# FiltrosGyrator_SCH.net
KiCad netlist of a schematic drawn in Altium Designer
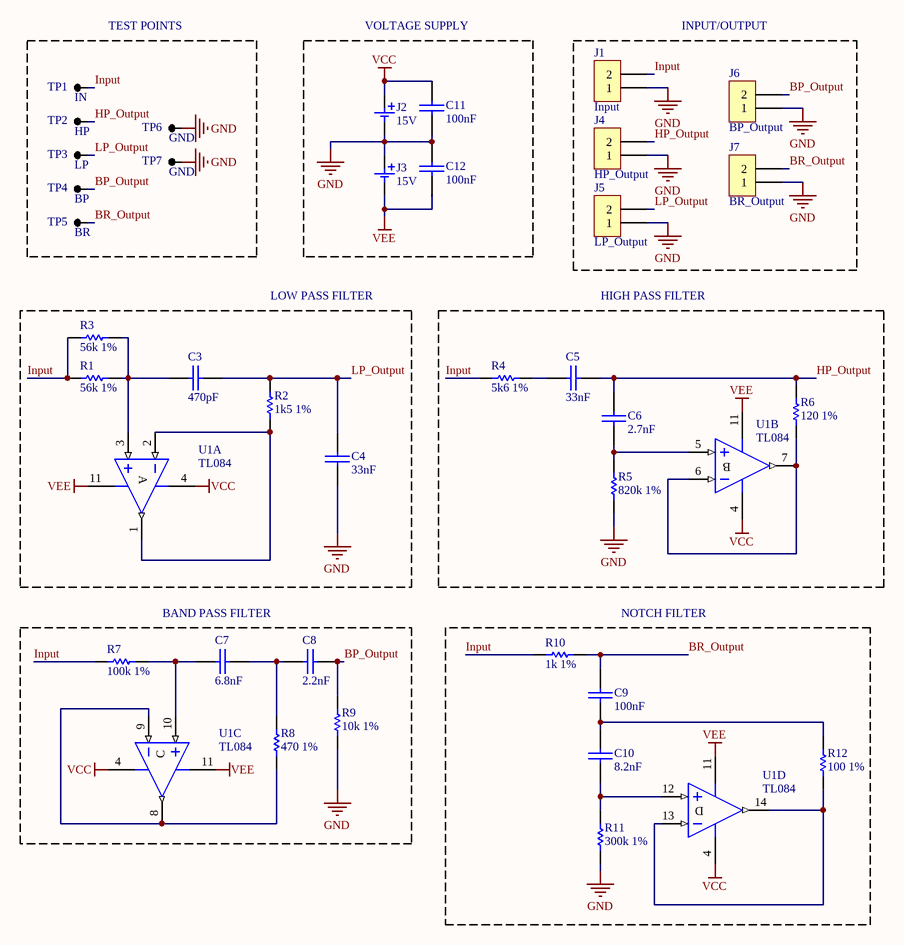
[diagram p0: FiltrosGyrator_SCH.SchDoc]

(export (version "E")
  (design (tool "Eeschema 10.0.6"))
  (components
    (comp (ref "C3")
      (value "470pF")
      (footprint "CAP_470p_CERAMIC_THT")
      (libsource (lib "LIBEBAL") (part "CAP"))
    )
    (comp (ref "C4") (value "33nF") (footprint "CAP_33N_FILM_THT") (libsource (lib "LIBEBAL") (part "CAP")))
    (comp (ref "C5") (value "33nF") (footprint "CAP_33N_FILM_THT") (libsource (lib "LIBEBAL") (part "CAP")))
    (comp (ref "C6") (value "2.7nF") (footprint "CAP_2.7n_FILM_THT") (libsource (lib "LIBEBAL") (part "CAP")))
    (comp (ref "C7") (value "6.8nF") (footprint "CAP_6.8n_FILM_THT") (libsource (lib "LIBEBAL") (part "CAP")))
    (comp (ref "C8") (value "2.2nF") (footprint "CAP_8.2n_FILM_THT") (libsource (lib "LIBEBAL") (part "CAP")))
    (comp (ref "C9") (value "100nF") (footprint "CAP_10N_FILM_THT") (libsource (lib "LIBEBAL") (part "CAP")))
    (comp (ref "C10")
      (value "8.2nF")
      (footprint "CAP_8.2n_FILM_THT")
      (libsource (lib "LIBEBAL") (part "CAP"))
    )
    (comp (ref "C11") (value "100nF") (footprint "0805") (libsource (lib "LIBEBAL") (part "CAP")))
    (comp (ref "C12") (value "100nF") (footprint "0805") (libsource (lib "LIBEBAL") (part "CAP")))
    (comp (ref "J1") (value "Input") (footprint "BORNERA2") (libsource (lib "LIB PIO IX") (part "BORNERA 2")))
    (comp (ref "J2")
      (value "15V")
      (footprint "BORNERA2")
      (description "BATERIA")
      (libsource (lib "LIBEBAL") (part "BATERIA"))
    )
    (comp (ref "J3")
      (value "15V")
      (footprint "BORNERA2")
      (description "BATERIA")
      (libsource (lib "LIBEBAL") (part "BATERIA"))
    )
    (comp (ref "J4")
      (value "HP_Output")
      (footprint "BORNERA2")
      (libsource (lib "LIB PIO IX") (part "BORNERA 2"))
    )
    (comp (ref "J5")
      (value "LP_Output")
      (footprint "BORNERA2")
      (libsource (lib "LIB PIO IX") (part "BORNERA 2"))
    )
    (comp (ref "J6")
      (value "BP_Output")
      (footprint "BORNERA2")
      (libsource (lib "LIB PIO IX") (part "BORNERA 2"))
    )
    (comp (ref "J7")
      (value "BR_Output")
      (footprint "BORNERA2")
      (libsource (lib "LIB PIO IX") (part "BORNERA 2"))
    )
    (comp (ref "R1") (value "56k 1%") (footprint "0805") (libsource (lib "LIBEBAL") (part "RES")))
    (comp (ref "R2") (value "1k5 1%") (footprint "0805") (libsource (lib "LIBEBAL") (part "RES")))
    (comp (ref "R3") (value "56k 1%") (footprint "0805") (libsource (lib "LIBEBAL") (part "RES")))
    (comp (ref "R4") (value "5k6 1%") (footprint "0805") (libsource (lib "LIBEBAL") (part "RES")))
    (comp (ref "R5") (value "820k 1%") (footprint "0805") (libsource (lib "LIBEBAL") (part "RES")))
    (comp (ref "R6") (value "120 1%") (footprint "0805") (libsource (lib "LIBEBAL") (part "RES")))
    (comp (ref "R7") (value "100k 1%") (footprint "0805") (libsource (lib "LIBEBAL") (part "RES")))
    (comp (ref "R8") (value "470 1%") (footprint "0805") (libsource (lib "LIBEBAL") (part "RES")))
    (comp (ref "R9") (value "10k 1%") (footprint "0805") (libsource (lib "LIBEBAL") (part "RES")))
    (comp (ref "R10") (value "1k 1%") (footprint "0805") (libsource (lib "LIBEBAL") (part "RES")))
    (comp (ref "R11") (value "300k 1%") (footprint "0805") (libsource (lib "LIBEBAL") (part "RES")))
    (comp (ref "R12") (value "100 1%") (footprint "0805") (libsource (lib "LIBEBAL") (part "RES")))
    (comp (ref "TP1") (value "IN") (footprint "TPTH") (libsource (lib "LIBEBAL") (part "TP")))
    (comp (ref "TP2") (value "HP") (footprint "TPTH") (libsource (lib "LIBEBAL") (part "TP")))
    (comp (ref "TP3") (value "LP") (footprint "TPTH") (libsource (lib "LIBEBAL") (part "TP")))
    (comp (ref "TP4") (value "BP") (footprint "TPTH") (libsource (lib "LIBEBAL") (part "TP")))
    (comp (ref "TP5") (value "BR") (footprint "TPTH") (libsource (lib "LIBEBAL") (part "TP")))
    (comp (ref "TP6") (value "GND") (footprint "TPTH") (libsource (lib "LIBEBAL") (part "TP")))
    (comp (ref "TP7") (value "GND") (footprint "TPTH") (libsource (lib "LIBEBAL") (part "TP")))
    (comp (ref "U1")
      (value "TL084")
      (footprint "J014")
      (description "JFET-Input Operational Amplifier")
      (fields (field (name "PUBLISHER") "Altium Limited"))
      (libsource (lib "FiltrosGyrator") (part "TL084J"))
    )
  )
  (nets
    (net (code "1") (name "/BP_Output") (class "Default")
      (node (ref "C8") (pin "2") (pinfunction "2_2") (pintype "passive"))
      (node (ref "J6") (pin "2") (pinfunction "2_2") (pintype "passive"))
      (node (ref "R9") (pin "2") (pinfunction "2_2") (pintype "passive"))
      (node (ref "TP4") (pin "1") (pinfunction "1_1") (pintype "passive"))
    )
    (net (code "2") (name "/BR_Output") (class "Default")
      (node (ref "C9") (pin "1") (pinfunction "1_1") (pintype "passive"))
      (node (ref "J7") (pin "2") (pinfunction "2_2") (pintype "passive"))
      (node (ref "R10") (pin "2") (pinfunction "2_2") (pintype "passive"))
      (node (ref "TP5") (pin "1") (pinfunction "1_1") (pintype "passive"))
    )
    (net (code "3") (name "/HP_Output") (class "Default")
      (node (ref "C5") (pin "2") (pinfunction "2_2") (pintype "passive"))
      (node (ref "C6") (pin "1") (pinfunction "1_1") (pintype "passive"))
      (node (ref "J4") (pin "2") (pinfunction "2_2") (pintype "passive"))
      (node (ref "R6") (pin "1") (pinfunction "1_1") (pintype "passive"))
      (node (ref "TP2") (pin "1") (pinfunction "1_1") (pintype "passive"))
    )
    (net (code "4") (name "/Input") (class "Default")
      (node (ref "J1") (pin "2") (pinfunction "2_2") (pintype "passive"))
      (node (ref "R1") (pin "1") (pinfunction "1_1") (pintype "passive"))
      (node (ref "R10") (pin "1") (pinfunction "1_1") (pintype "passive"))
      (node (ref "R3") (pin "1") (pinfunction "1_1") (pintype "passive"))
      (node (ref "R4") (pin "1") (pinfunction "1_1") (pintype "passive"))
      (node (ref "R7") (pin "1") (pinfunction "1_1") (pintype "passive"))
      (node (ref "TP1") (pin "1") (pinfunction "1_1") (pintype "passive"))
    )
    (net (code "5") (name "/LP_Output") (class "Default")
      (node (ref "C3") (pin "2") (pinfunction "2_2") (pintype "passive"))
      (node (ref "C4") (pin "2") (pinfunction "2_2") (pintype "passive"))
      (node (ref "J5") (pin "2") (pinfunction "2_2") (pintype "passive"))
      (node (ref "R2") (pin "2") (pinfunction "2_2") (pintype "passive"))
      (node (ref "TP3") (pin "1") (pinfunction "1_1") (pintype "passive"))
    )
    (net (code "6") (name "GND") (class "Default")
      (node (ref "C11") (pin "2") (pinfunction "2_2") (pintype "passive"))
      (node (ref "C12") (pin "1") (pinfunction "1_1") (pintype "passive"))
      (node (ref "C4") (pin "1") (pinfunction "1_1") (pintype "passive"))
      (node (ref "J1") (pin "1") (pinfunction "1_1") (pintype "passive"))
      (node (ref "J2") (pin "2") (pintype "passive"))
      (node (ref "J3") (pin "1") (pintype "passive"))
      (node (ref "J4") (pin "1") (pinfunction "1_1") (pintype "passive"))
      (node (ref "J5") (pin "1") (pinfunction "1_1") (pintype "passive"))
      (node (ref "J6") (pin "1") (pinfunction "1_1") (pintype "passive"))
      (node (ref "J7") (pin "1") (pinfunction "1_1") (pintype "passive"))
      (node (ref "R11") (pin "2") (pinfunction "2_2") (pintype "passive"))
      (node (ref "R5") (pin "1") (pinfunction "1_1") (pintype "passive"))
      (node (ref "R9") (pin "1") (pinfunction "1_1") (pintype "passive"))
      (node (ref "TP6") (pin "1") (pinfunction "1_1") (pintype "passive"))
      (node (ref "TP7") (pin "1") (pinfunction "1_1") (pintype "passive"))
    )
    (net (code "7") (name "Net-(C5-Pad1)") (class "Default")
      (node (ref "C5") (pin "1") (pinfunction "1_1") (pintype "passive"))
      (node (ref "R4") (pin "2") (pinfunction "2_2") (pintype "passive"))
    )
    (net (code "8") (name "Net-(C7-Pad2)") (class "Default")
      (node (ref "C7") (pin "2") (pinfunction "2_2") (pintype "passive"))
      (node (ref "C8") (pin "1") (pinfunction "1_1") (pintype "passive"))
      (node (ref "R8") (pin "2") (pinfunction "2_2") (pintype "passive"))
    )
    (net (code "9") (name "Net-(C10-Pad2)") (class "Default")
      (node (ref "C10") (pin "2") (pinfunction "2_2") (pintype "passive"))
      (node (ref "C9") (pin "2") (pinfunction "2_2") (pintype "passive"))
      (node (ref "R12") (pin "2") (pinfunction "2_2") (pintype "passive"))
    )
    (net (code "10") (name "Net-(U1A-IN+)") (class "Default")
      (node (ref "C3") (pin "1") (pinfunction "1_1") (pintype "passive"))
      (node (ref "R1") (pin "2") (pinfunction "2_2") (pintype "passive"))
      (node (ref "R3") (pin "2") (pinfunction "2_2") (pintype "passive"))
      (node (ref "U1") (pin "3") (pinfunction "IN+_3") (pintype "input"))
    )
    (net (code "11") (name "Net-(U1A-IN-)") (class "Default")
      (node (ref "R2") (pin "1") (pinfunction "1_1") (pintype "passive"))
      (node (ref "U1") (pin "1") (pinfunction "OUT_1") (pintype "output"))
      (node (ref "U1") (pin "2") (pinfunction "IN-_2") (pintype "input"))
    )
    (net (code "12") (name "Net-(U1B-IN+)") (class "Default")
      (node (ref "C6") (pin "2") (pinfunction "2_2") (pintype "passive"))
      (node (ref "R5") (pin "2") (pinfunction "2_2") (pintype "passive"))
      (node (ref "U1") (pin "5") (pinfunction "IN+_5") (pintype "input"))
    )
    (net (code "13") (name "Net-(U1B-IN-)") (class "Default")
      (node (ref "R6") (pin "2") (pinfunction "2_2") (pintype "passive"))
      (node (ref "U1") (pin "6") (pinfunction "IN-_6") (pintype "input"))
      (node (ref "U1") (pin "7") (pinfunction "OUT_7") (pintype "output"))
    )
    (net (code "14") (name "Net-(U1C-IN+)") (class "Default")
      (node (ref "C7") (pin "1") (pinfunction "1_1") (pintype "passive"))
      (node (ref "R7") (pin "2") (pinfunction "2_2") (pintype "passive"))
      (node (ref "U1") (pin "10") (pinfunction "IN+_10") (pintype "input"))
    )
    (net (code "15") (name "Net-(U1C-IN-)") (class "Default")
      (node (ref "R8") (pin "1") (pinfunction "1_1") (pintype "passive"))
      (node (ref "U1") (pin "8") (pinfunction "OUT_8") (pintype "output"))
      (node (ref "U1") (pin "9") (pinfunction "IN-_9") (pintype "input"))
    )
    (net (code "16") (name "Net-(U1D-IN+)") (class "Default")
      (node (ref "C10") (pin "1") (pinfunction "1_1") (pintype "passive"))
      (node (ref "R11") (pin "1") (pinfunction "1_1") (pintype "passive"))
      (node (ref "U1") (pin "12") (pinfunction "IN+_12") (pintype "input"))
    )
    (net (code "17") (name "Net-(U1D-IN-)") (class "Default")
      (node (ref "R12") (pin "1") (pinfunction "1_1") (pintype "passive"))
      (node (ref "U1") (pin "13") (pinfunction "IN-_13") (pintype "input"))
      (node (ref "U1") (pin "14") (pinfunction "OUT_14") (pintype "output"))
    )
    (net (code "18") (name "VCC") (class "Default")
      (node (ref "C11") (pin "1") (pinfunction "1_1") (pintype "passive"))
      (node (ref "J2") (pin "1") (pintype "passive"))
      (node (ref "U1") (pin "4") (pinfunction "V+_4") (pintype "power_in"))
    )
    (net (code "19") (name "VEE") (class "Default")
      (node (ref "C12") (pin "2") (pinfunction "2_2") (pintype "passive"))
      (node (ref "J3") (pin "2") (pintype "passive"))
      (node (ref "U1") (pin "11") (pinfunction "V-_11") (pintype "power_in"))
    )
  )
)
